# Main.net
KiCad netlist of a schematic drawn in Altium Designer
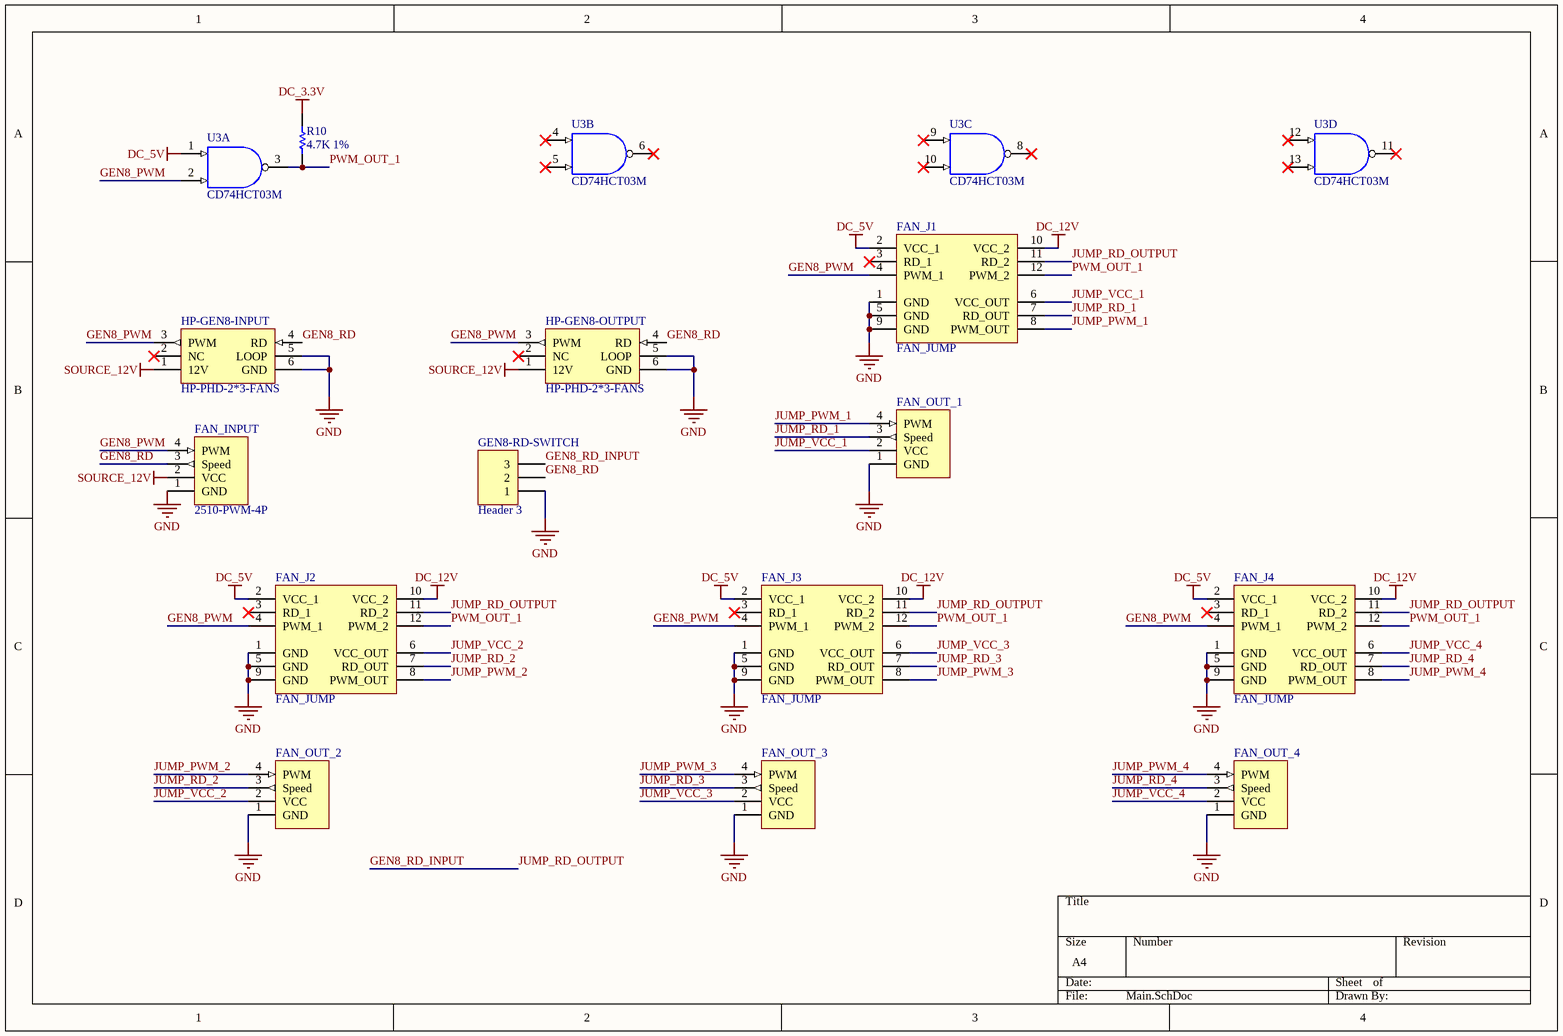
[diagram p0: Main.SchDoc]

(export (version "E")
  (design (tool "Eeschema 10.0.6"))
  (components
    (comp (ref "FAN_INPUT")
      (value "2510-PWM-4P")
      (footprint "2510-PWM-4PIN")
      (libsource (lib "Common") (part "2510-PWM-4P"))
    )
    (comp (ref "FAN_J1")
      (value "FAN_JUMP")
      (footprint "FAN_JUMP")
      (libsource (lib "Common") (part "FAN_JUMP"))
    )
    (comp (ref "FAN_J2")
      (value "FAN_JUMP")
      (footprint "FAN_JUMP")
      (libsource (lib "Common") (part "FAN_JUMP"))
    )
    (comp (ref "FAN_J3")
      (value "FAN_JUMP")
      (footprint "FAN_JUMP")
      (libsource (lib "Common") (part "FAN_JUMP"))
    )
    (comp (ref "FAN_J4")
      (value "FAN_JUMP")
      (footprint "FAN_JUMP")
      (libsource (lib "Common") (part "FAN_JUMP"))
    )
    (comp (ref "FAN_OUT_1")
      (value "~")
      (footprint "2510-PWM-4PIN")
      (libsource (lib "Common") (part "2510-PWM-4P"))
    )
    (comp (ref "FAN_OUT_2")
      (value "~")
      (footprint "2510-PWM-4PIN")
      (libsource (lib "Common") (part "2510-PWM-4P"))
    )
    (comp (ref "FAN_OUT_3")
      (value "~")
      (footprint "2510-PWM-4PIN")
      (libsource (lib "Common") (part "2510-PWM-4P"))
    )
    (comp (ref "FAN_OUT_4")
      (value "~")
      (footprint "2510-PWM-4PIN")
      (libsource (lib "Common") (part "2510-PWM-4P"))
    )
    (comp (ref "GEN8-RD-SWITCH")
      (value "Header 3")
      (footprint "HDR1X3")
      (description "Header, 3-Pin")
      (fields (field (name "PUBLISHER") "Altium Limited"))
      (libsource (lib "Miscellaneous Connectors") (part "Header 3"))
    )
    (comp (ref "HP-GEN8-INPUT")
      (value "HP-PHD-2*3-FANS")
      (footprint "PHD-2*3AW")
      (libsource (lib "Common") (part "HP-PHD-2*3-FANS"))
    )
    (comp (ref "HP-GEN8-OUTPUT")
      (value "HP-PHD-2*3-FANS")
      (footprint "PHD-2*3AW")
      (libsource (lib "Common") (part "HP-PHD-2*3-FANS"))
    )
    (comp (ref "R10")
      (value "4.7K 1%")
      (footprint "RESC0805(2012)_L")
      (fields (field (name "TOLERANCE") "1 %") (field (name "POWER") "0.125 W"))
      (libsource (lib "Altium Content Vault") (part "CMP-1013-00736-1"))
    )
    (comp (ref "U3")
      (value "CD74HCT03M")
      (footprint "D0014A_L")
      (description "High Speed CMOS Logic Quad 2-Input NAND Gates with Open Drain, D0014A, TUBE")
      (fields
        (field (name "MANUFACTURER") "Texas Instruments")
        (field (name "GENERIC PART NUMBER") "CD74HCT03")
      )
      (libsource (lib "Altium Content Vault") (part "CMP-1627-00022-2"))
    )
  )
  (nets
    (net (code "1") (name "/GEN8_PWM") (class "Default")
      (node (ref "FAN_INPUT") (pin "4") (pinfunction "PWM_4") (pintype "input"))
      (node (ref "FAN_J1") (pin "4") (pinfunction "PWM_1_4") (pintype "passive"))
      (node (ref "FAN_J2") (pin "4") (pinfunction "PWM_1_4") (pintype "passive"))
      (node (ref "FAN_J3") (pin "4") (pinfunction "PWM_1_4") (pintype "passive"))
      (node (ref "FAN_J4") (pin "4") (pinfunction "PWM_1_4") (pintype "passive"))
      (node (ref "HP-GEN8-INPUT") (pin "3") (pinfunction "PWM_3") (pintype "output"))
      (node (ref "HP-GEN8-OUTPUT") (pin "3") (pinfunction "PWM_3") (pintype "output"))
      (node (ref "U3") (pin "2") (pinfunction "1B_2") (pintype "input"))
    )
    (net (code "2") (name "/GEN8_RD") (class "Default")
      (node (ref "FAN_INPUT") (pin "3") (pinfunction "Speed_3") (pintype "output"))
      (node (ref "GEN8-RD-SWITCH") (pin "2") (pinfunction "2_2") (pintype "passive"))
      (node (ref "HP-GEN8-INPUT") (pin "4") (pinfunction "RD_4") (pintype "input"))
      (node (ref "HP-GEN8-OUTPUT") (pin "4") (pinfunction "RD_4") (pintype "input"))
    )
    (net (code "3") (name "/GEN8_RD_INPUT") (class "Default")
      (node (ref "FAN_J1") (pin "11") (pinfunction "RD_2_11") (pintype "passive"))
      (node (ref "FAN_J2") (pin "11") (pinfunction "RD_2_11") (pintype "passive"))
      (node (ref "FAN_J3") (pin "11") (pinfunction "RD_2_11") (pintype "passive"))
      (node (ref "FAN_J4") (pin "11") (pinfunction "RD_2_11") (pintype "passive"))
      (node (ref "GEN8-RD-SWITCH") (pin "3") (pinfunction "3_3") (pintype "passive"))
    )
    (net (code "4") (name "/JUMP_PWM_1") (class "Default")
      (node (ref "FAN_J1") (pin "8") (pinfunction "PWM_OUT_8") (pintype "passive"))
      (node (ref "FAN_OUT_1") (pin "4") (pinfunction "PWM_4") (pintype "input"))
    )
    (net (code "5") (name "/JUMP_PWM_2") (class "Default")
      (node (ref "FAN_J2") (pin "8") (pinfunction "PWM_OUT_8") (pintype "passive"))
      (node (ref "FAN_OUT_2") (pin "4") (pinfunction "PWM_4") (pintype "input"))
    )
    (net (code "6") (name "/JUMP_PWM_3") (class "Default")
      (node (ref "FAN_J3") (pin "8") (pinfunction "PWM_OUT_8") (pintype "passive"))
      (node (ref "FAN_OUT_3") (pin "4") (pinfunction "PWM_4") (pintype "input"))
    )
    (net (code "7") (name "/JUMP_PWM_4") (class "Default")
      (node (ref "FAN_J4") (pin "8") (pinfunction "PWM_OUT_8") (pintype "passive"))
      (node (ref "FAN_OUT_4") (pin "4") (pinfunction "PWM_4") (pintype "input"))
    )
    (net (code "8") (name "/JUMP_RD_1") (class "Default")
      (node (ref "FAN_J1") (pin "7") (pinfunction "RD_OUT_7") (pintype "passive"))
      (node (ref "FAN_OUT_1") (pin "3") (pinfunction "Speed_3") (pintype "output"))
    )
    (net (code "9") (name "/JUMP_RD_2") (class "Default")
      (node (ref "FAN_J2") (pin "7") (pinfunction "RD_OUT_7") (pintype "passive"))
      (node (ref "FAN_OUT_2") (pin "3") (pinfunction "Speed_3") (pintype "output"))
    )
    (net (code "10") (name "/JUMP_RD_3") (class "Default")
      (node (ref "FAN_J3") (pin "7") (pinfunction "RD_OUT_7") (pintype "passive"))
      (node (ref "FAN_OUT_3") (pin "3") (pinfunction "Speed_3") (pintype "output"))
    )
    (net (code "11") (name "/JUMP_RD_4") (class "Default")
      (node (ref "FAN_J4") (pin "7") (pinfunction "RD_OUT_7") (pintype "passive"))
      (node (ref "FAN_OUT_4") (pin "3") (pinfunction "Speed_3") (pintype "output"))
    )
    (net (code "12") (name "/JUMP_VCC_1") (class "Default")
      (node (ref "FAN_J1") (pin "6") (pinfunction "VCC_OUT_6") (pintype "passive"))
      (node (ref "FAN_OUT_1") (pin "2") (pinfunction "VCC_2") (pintype "power_in"))
    )
    (net (code "13") (name "/JUMP_VCC_2") (class "Default")
      (node (ref "FAN_J2") (pin "6") (pinfunction "VCC_OUT_6") (pintype "passive"))
      (node (ref "FAN_OUT_2") (pin "2") (pinfunction "VCC_2") (pintype "power_in"))
    )
    (net (code "14") (name "/JUMP_VCC_3") (class "Default")
      (node (ref "FAN_J3") (pin "6") (pinfunction "VCC_OUT_6") (pintype "passive"))
      (node (ref "FAN_OUT_3") (pin "2") (pinfunction "VCC_2") (pintype "power_in"))
    )
    (net (code "15") (name "/JUMP_VCC_4") (class "Default")
      (node (ref "FAN_J4") (pin "6") (pinfunction "VCC_OUT_6") (pintype "passive"))
      (node (ref "FAN_OUT_4") (pin "2") (pinfunction "VCC_2") (pintype "power_in"))
    )
    (net (code "16") (name "/PWM_OUT_1") (class "Default")
      (node (ref "FAN_J1") (pin "12") (pinfunction "PWM_2_12") (pintype "passive"))
      (node (ref "FAN_J2") (pin "12") (pinfunction "PWM_2_12") (pintype "passive"))
      (node (ref "FAN_J3") (pin "12") (pinfunction "PWM_2_12") (pintype "passive"))
      (node (ref "FAN_J4") (pin "12") (pinfunction "PWM_2_12") (pintype "passive"))
      (node (ref "R10") (pin "1") (pinfunction "1_1") (pintype "passive"))
      (node (ref "U3") (pin "3") (pinfunction "1Y_3") (pintype "open_collector"))
    )
    (net (code "17") (name "DC_3.3V") (class "Default")
      (node (ref "R10") (pin "2") (pinfunction "2_2") (pintype "passive"))
    )
    (net (code "18") (name "DC_5V") (class "Default")
      (node (ref "FAN_J1") (pin "2") (pinfunction "VCC_1_2") (pintype "passive"))
      (node (ref "FAN_J2") (pin "2") (pinfunction "VCC_1_2") (pintype "passive"))
      (node (ref "FAN_J3") (pin "2") (pinfunction "VCC_1_2") (pintype "passive"))
      (node (ref "FAN_J4") (pin "2") (pinfunction "VCC_1_2") (pintype "passive"))
      (node (ref "U3") (pin "1") (pinfunction "1A_1") (pintype "input"))
    )
    (net (code "19") (name "DC_12V") (class "Default")
      (node (ref "FAN_J1") (pin "10") (pinfunction "VCC_2_10") (pintype "passive"))
      (node (ref "FAN_J2") (pin "10") (pinfunction "VCC_2_10") (pintype "passive"))
      (node (ref "FAN_J3") (pin "10") (pinfunction "VCC_2_10") (pintype "passive"))
      (node (ref "FAN_J4") (pin "10") (pinfunction "VCC_2_10") (pintype "passive"))
    )
    (net (code "20") (name "GND") (class "Default")
      (node (ref "FAN_INPUT") (pin "1") (pinfunction "GND_1") (pintype "passive"))
      (node (ref "FAN_J1") (pin "1") (pinfunction "GND_1") (pintype "passive"))
      (node (ref "FAN_J1") (pin "5") (pinfunction "GND_5") (pintype "passive"))
      (node (ref "FAN_J1") (pin "9") (pinfunction "GND_9") (pintype "passive"))
      (node (ref "FAN_J2") (pin "1") (pinfunction "GND_1") (pintype "passive"))
      (node (ref "FAN_J2") (pin "5") (pinfunction "GND_5") (pintype "passive"))
      (node (ref "FAN_J2") (pin "9") (pinfunction "GND_9") (pintype "passive"))
      (node (ref "FAN_J3") (pin "1") (pinfunction "GND_1") (pintype "passive"))
      (node (ref "FAN_J3") (pin "5") (pinfunction "GND_5") (pintype "passive"))
      (node (ref "FAN_J3") (pin "9") (pinfunction "GND_9") (pintype "passive"))
      (node (ref "FAN_J4") (pin "1") (pinfunction "GND_1") (pintype "passive"))
      (node (ref "FAN_J4") (pin "5") (pinfunction "GND_5") (pintype "passive"))
      (node (ref "FAN_J4") (pin "9") (pinfunction "GND_9") (pintype "passive"))
      (node (ref "FAN_OUT_1") (pin "1") (pinfunction "GND_1") (pintype "passive"))
      (node (ref "FAN_OUT_2") (pin "1") (pinfunction "GND_1") (pintype "passive"))
      (node (ref "FAN_OUT_3") (pin "1") (pinfunction "GND_1") (pintype "passive"))
      (node (ref "FAN_OUT_4") (pin "1") (pinfunction "GND_1") (pintype "passive"))
      (node (ref "GEN8-RD-SWITCH") (pin "1") (pinfunction "1_1") (pintype "passive"))
      (node (ref "HP-GEN8-INPUT") (pin "5") (pinfunction "LOOP_5") (pintype "passive"))
      (node (ref "HP-GEN8-INPUT") (pin "6") (pinfunction "GND_6") (pintype "passive"))
      (node (ref "HP-GEN8-OUTPUT") (pin "5") (pinfunction "LOOP_5") (pintype "passive"))
      (node (ref "HP-GEN8-OUTPUT") (pin "6") (pinfunction "GND_6") (pintype "passive"))
    )
    (net (code "21") (name "SOURCE_12V") (class "Default")
      (node (ref "FAN_INPUT") (pin "2") (pinfunction "VCC_2") (pintype "power_in"))
      (node (ref "HP-GEN8-INPUT") (pin "1") (pinfunction "12V_1") (pintype "power_in"))
      (node (ref "HP-GEN8-OUTPUT") (pin "1") (pinfunction "12V_1") (pintype "power_in"))
    )
    (net (code "22") (name "unconnected-(FAN_J1-RD_1-Pad3)") (class "Default")
      (node (ref "FAN_J1") (pin "3") (pinfunction "RD_1_3") (pintype "passive+no_connect"))
    )
    (net (code "23") (name "unconnected-(FAN_J2-RD_1-Pad3)") (class "Default")
      (node (ref "FAN_J2") (pin "3") (pinfunction "RD_1_3") (pintype "passive+no_connect"))
    )
    (net (code "24") (name "unconnected-(FAN_J3-RD_1-Pad3)") (class "Default")
      (node (ref "FAN_J3") (pin "3") (pinfunction "RD_1_3") (pintype "passive+no_connect"))
    )
    (net (code "25") (name "unconnected-(FAN_J4-RD_1-Pad3)") (class "Default")
      (node (ref "FAN_J4") (pin "3") (pinfunction "RD_1_3") (pintype "passive+no_connect"))
    )
    (net (code "26") (name "unconnected-(HP-GEN8-INPUT-NC-Pad2)") (class "Default")
      (node (ref "HP-GEN8-INPUT") (pin "2") (pinfunction "NC_2") (pintype "passive+no_connect"))
    )
    (net (code "27") (name "unconnected-(HP-GEN8-OUTPUT-NC-Pad2)") (class "Default")
      (node (ref "HP-GEN8-OUTPUT") (pin "2") (pinfunction "NC_2") (pintype "passive+no_connect"))
    )
    (net (code "28") (name "unconnected-(U3B-2A-Pad4)") (class "Default")
      (node (ref "U3") (pin "4") (pinfunction "2A_4") (pintype "input+no_connect"))
    )
    (net (code "29") (name "unconnected-(U3B-2B-Pad5)") (class "Default")
      (node (ref "U3") (pin "5") (pinfunction "2B_5") (pintype "input+no_connect"))
    )
    (net (code "30") (name "unconnected-(U3B-2Y-Pad6)") (class "Default")
      (node (ref "U3") (pin "6") (pinfunction "2Y_6") (pintype "open_collector+no_connect"))
    )
    (net (code "31") (name "unconnected-(U3C-3A-Pad9)") (class "Default")
      (node (ref "U3") (pin "9") (pinfunction "3A_9") (pintype "input+no_connect"))
    )
    (net (code "32") (name "unconnected-(U3C-3B-Pad10)") (class "Default")
      (node (ref "U3") (pin "10") (pinfunction "3B_10") (pintype "input+no_connect"))
    )
    (net (code "33") (name "unconnected-(U3C-3Y-Pad8)") (class "Default")
      (node (ref "U3") (pin "8") (pinfunction "3Y_8") (pintype "open_collector+no_connect"))
    )
    (net (code "34") (name "unconnected-(U3D-4A-Pad12)") (class "Default")
      (node (ref "U3") (pin "12") (pinfunction "4A_12") (pintype "input+no_connect"))
    )
    (net (code "35") (name "unconnected-(U3D-4B-Pad13)") (class "Default")
      (node (ref "U3") (pin "13") (pinfunction "4B_13") (pintype "input+no_connect"))
    )
    (net (code "36") (name "unconnected-(U3D-4Y-Pad11)") (class "Default")
      (node (ref "U3") (pin "11") (pinfunction "4Y_11") (pintype "open_collector+no_connect"))
    )
  )
)
